# KlingelESP32V1.net
KiCad netlist of a schematic drawn in EAGLE
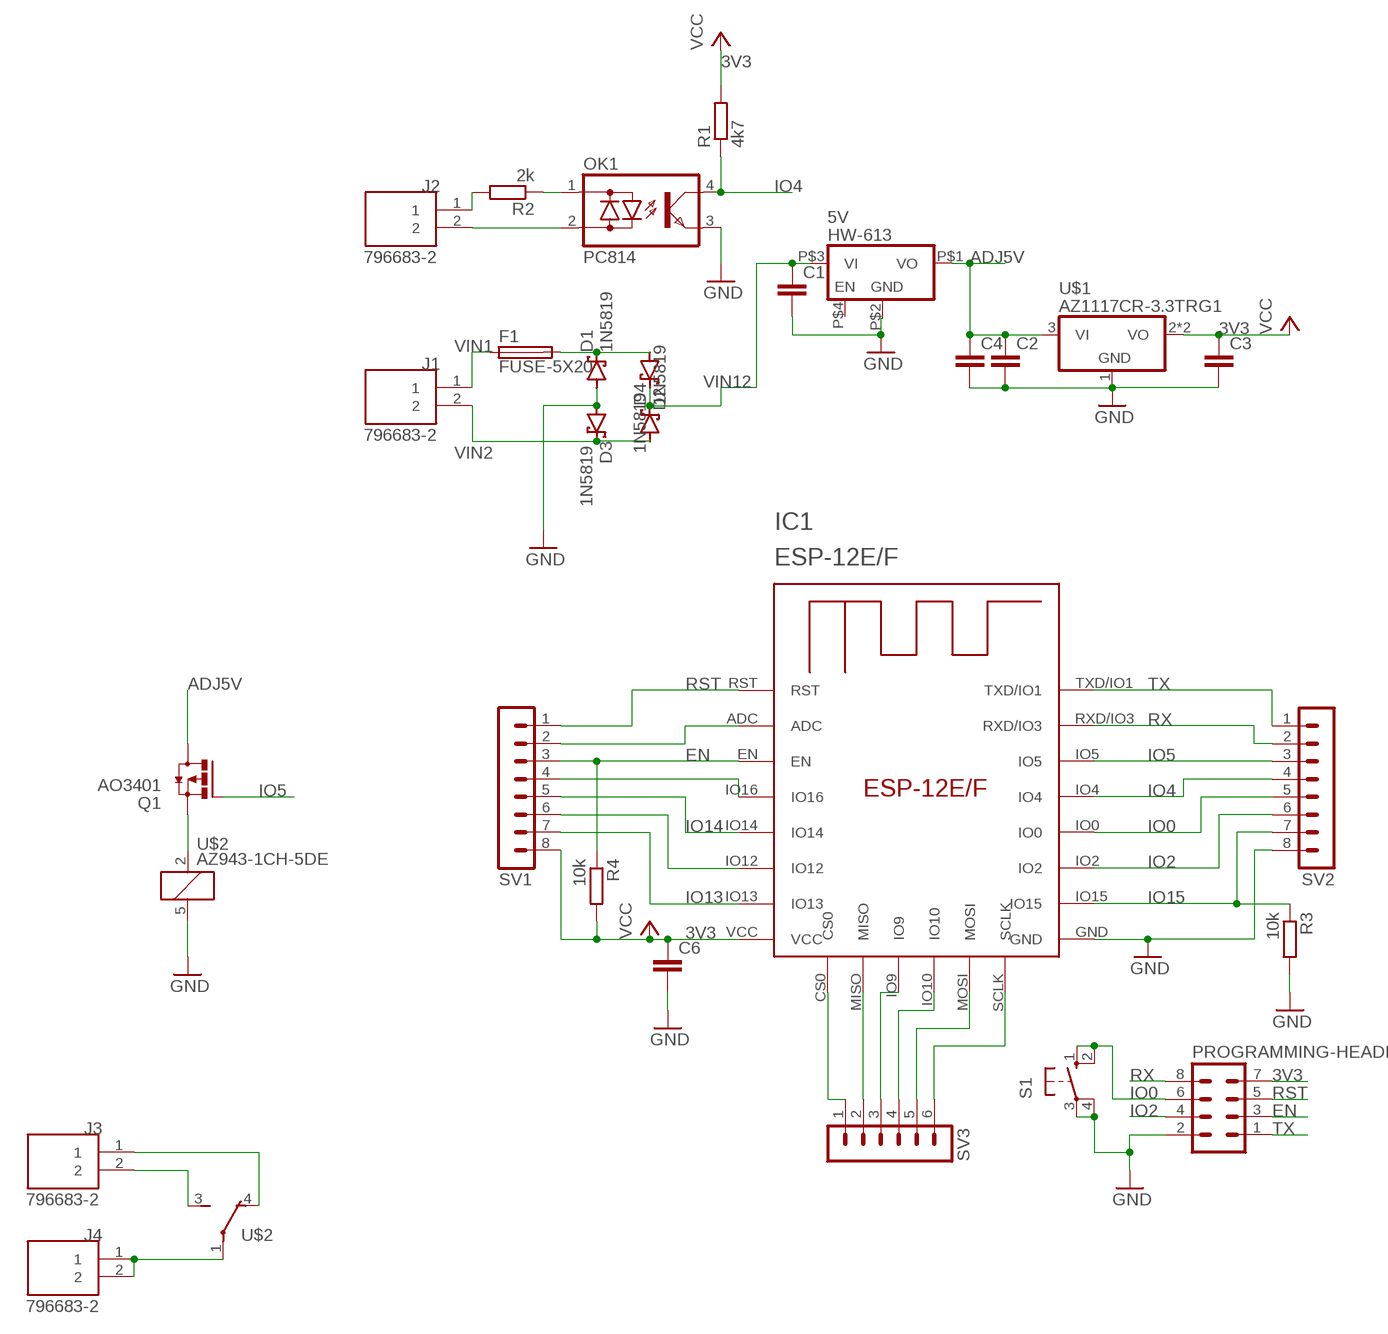
[diagram p0: schematic, sheet 1]

(export (version "E")
  (design (tool "Eeschema 10.0.6"))
  (components
    (comp (ref "5V")
      (value "HW-613")
      (footprint "eagle-import:HW-613")
      (libsource (lib "eagle-import") (part "HW-613"))
    )
    (comp (ref "C1")
      (value "C-EUC0805")
      (footprint "eagle-import:C0805")
      (libsource (lib "eagle-import") (part "C-EUC0805"))
    )
    (comp (ref "C2")
      (value "C-EUC0805")
      (footprint "eagle-import:C0805")
      (libsource (lib "eagle-import") (part "C-EUC0805"))
    )
    (comp (ref "C3")
      (value "C-EUC0805")
      (footprint "eagle-import:C0805")
      (libsource (lib "eagle-import") (part "C-EUC0805"))
    )
    (comp (ref "C4")
      (value "C-EUC0805")
      (footprint "eagle-import:C0805")
      (libsource (lib "eagle-import") (part "C-EUC0805"))
    )
    (comp (ref "C6")
      (value "C-EUC0805")
      (footprint "eagle-import:C0805")
      (libsource (lib "eagle-import") (part "C-EUC0805"))
    )
    (comp (ref "D1")
      (value "1N5819")
      (footprint "eagle-import:DO41-7.6")
      (libsource (lib "eagle-import") (part "1N5819-B"))
    )
    (comp (ref "D2")
      (value "1N5819")
      (footprint "eagle-import:DO41-7.6")
      (libsource (lib "eagle-import") (part "1N5819-B"))
    )
    (comp (ref "D3")
      (value "1N5819")
      (footprint "eagle-import:DO41-7.6")
      (libsource (lib "eagle-import") (part "1N5819-B"))
    )
    (comp (ref "D4")
      (value "1N5819")
      (footprint "eagle-import:DO41-7.6")
      (libsource (lib "eagle-import") (part "1N5819-B"))
    )
    (comp (ref "F1")
      (value "FUSE-5X20")
      (footprint "eagle-import:0751.0052")
      (libsource (lib "eagle-import") (part "FUSE-5X20"))
    )
    (comp (ref "IC1")
      (value "ESP-12E/F")
      (footprint "eagle-import:ESP-12E")
      (libsource (lib "eagle-import") (part "ESP-12E/F"))
    )
    (comp (ref "J1")
      (value "796683-2")
      (footprint "eagle-import:TE_796683-2")
      (fields (field (name "MF") "TE Connectivity"))
      (libsource (lib "eagle-import") (part "796683-2"))
    )
    (comp (ref "J2")
      (value "796683-2")
      (footprint "eagle-import:TE_796683-2")
      (fields (field (name "MF") "TE Connectivity"))
      (libsource (lib "eagle-import") (part "796683-2"))
    )
    (comp (ref "J3")
      (value "796683-2")
      (footprint "eagle-import:TE_796683-2")
      (fields (field (name "MF") "TE Connectivity"))
      (libsource (lib "eagle-import") (part "796683-2"))
    )
    (comp (ref "J4")
      (value "796683-2")
      (footprint "eagle-import:TE_796683-2")
      (fields (field (name "MF") "TE Connectivity"))
      (libsource (lib "eagle-import") (part "796683-2"))
    )
    (comp (ref "OK1")
      (value "PC814")
      (footprint "eagle-import:DIL04")
      (libsource (lib "eagle-import") (part "PC814"))
    )
    (comp (ref "PROGRAMMING-HEADER")
      (value "MA04-2")
      (footprint "eagle-import:MA04-2")
      (libsource (lib "eagle-import") (part "MA04-2"))
    )
    (comp (ref "Q1")
      (value "AO3401")
      (footprint "eagle-import:SUPER-SOT3")
      (libsource (lib "eagle-import") (part "FDN360P"))
    )
    (comp (ref "R1")
      (value "4k7")
      (footprint "eagle-import:R0805")
      (libsource (lib "eagle-import") (part "R-EU_R0805"))
    )
    (comp (ref "R2")
      (value "2k")
      (footprint "eagle-import:R0805")
      (libsource (lib "eagle-import") (part "R-EU_R0805"))
    )
    (comp (ref "R3")
      (value "10k")
      (footprint "eagle-import:R0805")
      (libsource (lib "eagle-import") (part "R-EU_R0805"))
    )
    (comp (ref "R4")
      (value "10k")
      (footprint "eagle-import:R0805")
      (libsource (lib "eagle-import") (part "R-EU_R0805"))
    )
    (comp (ref "S1")
      (value "10-XX")
      (footprint "eagle-import:B3F-10XX")
      (fields (field (name "MPN") "B3F-1000"))
      (libsource (lib "eagle-import") (part "10-XX"))
    )
    (comp (ref "SV1")
      (value "MA08-1")
      (footprint "eagle-import:MA08-1")
      (libsource (lib "eagle-import") (part "MA08-1"))
    )
    (comp (ref "SV2")
      (value "MA08-1")
      (footprint "eagle-import:MA08-1")
      (libsource (lib "eagle-import") (part "MA08-1"))
    )
    (comp (ref "SV3")
      (value "MA06-1")
      (footprint "eagle-import:MA06-1")
      (libsource (lib "eagle-import") (part "MA06-1"))
    )
    (comp (ref "U$1")
      (value "AZ1117CR-3.3TRG1")
      (footprint "eagle-import:SOT89")
      (libsource (lib "eagle-import") (part "AZ1117CR-3.3TRG1"))
    )
    (comp (ref "U$2")
      (value "AZ943-1CH-5DE")
      (footprint "eagle-import:AZ943-1CH-5DE")
      (libsource (lib "eagle-import") (part "AZ943-1CH-5DE"))
    )
  )
  (nets
    (net (code "1") (name "/ADJ5V") (class "Default")
      (node (ref "5V") (pin "P$1") (pinfunction "VO_P$1") (pintype "passive"))
      (node (ref "C2") (pin "1") (pinfunction "1_1") (pintype "passive"))
      (node (ref "C4") (pin "1") (pinfunction "1_1") (pintype "passive"))
      (node (ref "Q1") (pin "3") (pinfunction "D_3") (pintype "passive"))
      (node (ref "U$1") (pin "3") (pinfunction "VI_3") (pintype "input"))
    )
    (net (code "2") (name "/EN") (class "Default")
      (node (ref "IC1") (pin "EN") (pinfunction "EN_EN") (pintype "bidirectional"))
      (node (ref "PROGRAMMING-HEADER") (pin "3") (pinfunction "3_3") (pintype "passive"))
      (node (ref "R4") (pin "1") (pinfunction "1_1") (pintype "passive"))
      (node (ref "SV1") (pin "3") (pinfunction "3_3") (pintype "passive"))
    )
    (net (code "3") (name "/IO0") (class "Default")
      (node (ref "IC1") (pin "IO0") (pinfunction "IO0_IO0") (pintype "bidirectional"))
      (node (ref "PROGRAMMING-HEADER") (pin "6") (pinfunction "6_6") (pintype "passive"))
      (node (ref "S1") (pin "1") (pinfunction "S_1") (pintype "passive"))
      (node (ref "S1") (pin "2") (pinfunction "S1_2") (pintype "passive"))
      (node (ref "SV2") (pin "5") (pinfunction "5_5") (pintype "passive"))
    )
    (net (code "4") (name "/IO2") (class "Default")
      (node (ref "IC1") (pin "IO2") (pinfunction "IO2_IO2") (pintype "bidirectional"))
      (node (ref "PROGRAMMING-HEADER") (pin "4") (pinfunction "4_4") (pintype "passive"))
      (node (ref "SV2") (pin "6") (pinfunction "6_6") (pintype "passive"))
    )
    (net (code "5") (name "/IO4") (class "Default")
      (node (ref "IC1") (pin "IO4") (pinfunction "IO4_IO4") (pintype "bidirectional"))
      (node (ref "OK1") (pin "4") (pinfunction "C_4") (pintype "passive"))
      (node (ref "R1") (pin "1") (pinfunction "1_1") (pintype "passive"))
      (node (ref "SV2") (pin "4") (pinfunction "4_4") (pintype "passive"))
    )
    (net (code "6") (name "/IO5") (class "Default")
      (node (ref "IC1") (pin "IO5") (pinfunction "IO5_IO5") (pintype "bidirectional"))
      (node (ref "Q1") (pin "1") (pinfunction "G_1") (pintype "passive"))
      (node (ref "SV2") (pin "3") (pinfunction "3_3") (pintype "passive"))
    )
    (net (code "7") (name "/IO13") (class "Default")
      (node (ref "IC1") (pin "IO13") (pinfunction "IO13_IO13") (pintype "bidirectional"))
      (node (ref "SV1") (pin "7") (pinfunction "7_7") (pintype "passive"))
    )
    (net (code "8") (name "/IO14") (class "Default")
      (node (ref "IC1") (pin "IO14") (pinfunction "IO14_IO14") (pintype "bidirectional"))
      (node (ref "SV1") (pin "5") (pinfunction "5_5") (pintype "passive"))
    )
    (net (code "9") (name "/IO15") (class "Default")
      (node (ref "IC1") (pin "IO15") (pinfunction "IO15_IO15") (pintype "bidirectional"))
      (node (ref "R3") (pin "1") (pinfunction "1_1") (pintype "passive"))
      (node (ref "SV2") (pin "7") (pinfunction "7_7") (pintype "passive"))
    )
    (net (code "10") (name "/RST") (class "Default")
      (node (ref "IC1") (pin "RST") (pinfunction "RST_RST") (pintype "input"))
      (node (ref "PROGRAMMING-HEADER") (pin "5") (pinfunction "5_5") (pintype "passive"))
      (node (ref "SV1") (pin "1") (pinfunction "1_1") (pintype "passive"))
    )
    (net (code "11") (name "/RX") (class "Default")
      (node (ref "IC1") (pin "RXD/IO3") (pinfunction "RXD/IO3_RXD/IO3") (pintype "bidirectional"))
      (node (ref "PROGRAMMING-HEADER") (pin "8") (pinfunction "8_8") (pintype "passive"))
      (node (ref "SV2") (pin "2") (pinfunction "2_2") (pintype "passive"))
    )
    (net (code "12") (name "/TX") (class "Default")
      (node (ref "IC1") (pin "TXD/IO1") (pinfunction "TXD/IO1_TXD/IO1") (pintype "bidirectional"))
      (node (ref "PROGRAMMING-HEADER") (pin "1") (pinfunction "1_1") (pintype "passive"))
      (node (ref "SV2") (pin "1") (pinfunction "1_1") (pintype "passive"))
    )
    (net (code "13") (name "/VIN1") (class "Default")
      (node (ref "F1") (pin "P$1") (pinfunction "1_P$1") (pintype "passive"))
      (node (ref "F1") (pin "P$2") (pinfunction "1_P$2") (pintype "passive"))
      (node (ref "J1") (pin "1") (pinfunction "1_1") (pintype "passive"))
    )
    (net (code "14") (name "/VIN2") (class "Default")
      (node (ref "D3") (pin "C") (pinfunction "C_C") (pintype "passive"))
      (node (ref "D4") (pin "A") (pinfunction "A_A") (pintype "passive"))
      (node (ref "J1") (pin "2") (pinfunction "2_2") (pintype "passive"))
    )
    (net (code "15") (name "/VIN12") (class "Default")
      (node (ref "5V") (pin "P$3") (pinfunction "VI_P$3") (pintype "input"))
      (node (ref "C1") (pin "1") (pinfunction "1_1") (pintype "passive"))
      (node (ref "D2") (pin "C") (pinfunction "C_C") (pintype "passive"))
      (node (ref "D4") (pin "C") (pinfunction "C_C") (pintype "passive"))
    )
    (net (code "16") (name "GND") (class "Default")
      (node (ref "5V") (pin "P$2") (pinfunction "ADJ1_P$2") (pintype "power_in"))
      (node (ref "C1") (pin "2") (pinfunction "2_2") (pintype "passive"))
      (node (ref "C2") (pin "2") (pinfunction "2_2") (pintype "passive"))
      (node (ref "C3") (pin "2") (pinfunction "2_2") (pintype "passive"))
      (node (ref "C4") (pin "2") (pinfunction "2_2") (pintype "passive"))
      (node (ref "C6") (pin "2") (pinfunction "2_2") (pintype "passive"))
      (node (ref "D1") (pin "A") (pinfunction "A_A") (pintype "passive"))
      (node (ref "D3") (pin "A") (pinfunction "A_A") (pintype "passive"))
      (node (ref "IC1") (pin "GND") (pinfunction "GND_GND") (pintype "power_in"))
      (node (ref "OK1") (pin "3") (pinfunction "E_3") (pintype "passive"))
      (node (ref "PROGRAMMING-HEADER") (pin "2") (pinfunction "2_2") (pintype "passive"))
      (node (ref "R3") (pin "2") (pinfunction "2_2") (pintype "passive"))
      (node (ref "S1") (pin "3") (pinfunction "P_3") (pintype "passive"))
      (node (ref "S1") (pin "4") (pinfunction "P1_4") (pintype "passive"))
      (node (ref "SV2") (pin "8") (pinfunction "8_8") (pintype "passive"))
      (node (ref "U$1") (pin "1") (pinfunction "GND_1") (pintype "power_in"))
      (node (ref "U$2") (pin "5") (pinfunction "2_5") (pintype "passive"))
    )
    (net (code "17") (name "Net-(D1-PadC)") (class "Default")
      (node (ref "D1") (pin "C") (pinfunction "C_C") (pintype "passive"))
      (node (ref "D2") (pin "A") (pinfunction "A_A") (pintype "passive"))
      (node (ref "F1") (pin "P$3") (pinfunction "2_P$3") (pintype "passive"))
      (node (ref "F1") (pin "P$4") (pinfunction "2_P$4") (pintype "passive"))
    )
    (net (code "18") (name "Net-(IC1-PadADC)") (class "Default")
      (node (ref "IC1") (pin "ADC") (pinfunction "ADC_ADC") (pintype "bidirectional"))
      (node (ref "SV1") (pin "2") (pinfunction "2_2") (pintype "passive"))
    )
    (net (code "19") (name "Net-(IC1-PadCS0)") (class "Default")
      (node (ref "IC1") (pin "CS0") (pinfunction "CS0_CS0") (pintype "bidirectional"))
      (node (ref "SV3") (pin "1") (pinfunction "1_1") (pintype "passive"))
    )
    (net (code "20") (name "Net-(IC1-PadIO9)") (class "Default")
      (node (ref "IC1") (pin "IO9") (pinfunction "IO9_IO9") (pintype "bidirectional"))
      (node (ref "SV3") (pin "3") (pinfunction "3_3") (pintype "passive"))
    )
    (net (code "21") (name "Net-(IC1-PadIO10)") (class "Default")
      (node (ref "IC1") (pin "IO10") (pinfunction "IO10_IO10") (pintype "bidirectional"))
      (node (ref "SV3") (pin "4") (pinfunction "4_4") (pintype "passive"))
    )
    (net (code "22") (name "Net-(IC1-PadIO12)") (class "Default")
      (node (ref "IC1") (pin "IO12") (pinfunction "IO12_IO12") (pintype "bidirectional"))
      (node (ref "SV1") (pin "6") (pinfunction "6_6") (pintype "passive"))
    )
    (net (code "23") (name "Net-(IC1-PadIO16)") (class "Default")
      (node (ref "IC1") (pin "IO16") (pinfunction "IO16_IO16") (pintype "bidirectional"))
      (node (ref "SV1") (pin "4") (pinfunction "4_4") (pintype "passive"))
    )
    (net (code "24") (name "Net-(IC1-PadMISO)") (class "Default")
      (node (ref "IC1") (pin "MISO") (pinfunction "MISO_MISO") (pintype "bidirectional"))
      (node (ref "SV3") (pin "2") (pinfunction "2_2") (pintype "passive"))
    )
    (net (code "25") (name "Net-(IC1-PadMOSI)") (class "Default")
      (node (ref "IC1") (pin "MOSI") (pinfunction "MOSI_MOSI") (pintype "bidirectional"))
      (node (ref "SV3") (pin "5") (pinfunction "5_5") (pintype "passive"))
    )
    (net (code "26") (name "Net-(IC1-PadSCLK)") (class "Default")
      (node (ref "IC1") (pin "SCLK") (pinfunction "SCLK_SCLK") (pintype "bidirectional"))
      (node (ref "SV3") (pin "6") (pinfunction "6_6") (pintype "passive"))
    )
    (net (code "27") (name "Net-(J2-Pad1)") (class "Default")
      (node (ref "J2") (pin "1") (pinfunction "1_1") (pintype "passive"))
      (node (ref "R2") (pin "2") (pinfunction "2_2") (pintype "passive"))
    )
    (net (code "28") (name "Net-(OK1-AC1)") (class "Default")
      (node (ref "OK1") (pin "1") (pinfunction "AC1_1") (pintype "passive"))
      (node (ref "R2") (pin "1") (pinfunction "1_1") (pintype "passive"))
    )
    (net (code "29") (name "Net-(OK1-AC2)") (class "Default")
      (node (ref "J2") (pin "2") (pinfunction "2_2") (pintype "passive"))
      (node (ref "OK1") (pin "2") (pinfunction "AC2_2") (pintype "passive"))
    )
    (net (code "30") (name "Net-(Q1-S)") (class "Default")
      (node (ref "Q1") (pin "2") (pinfunction "S_2") (pintype "passive"))
      (node (ref "U$2") (pin "2") (pinfunction "1_2") (pintype "passive"))
    )
    (net (code "31") (name "Net-(U$2B-O)") (class "Default")
      (node (ref "J3") (pin "1") (pinfunction "1_1") (pintype "passive"))
      (node (ref "U$2") (pin "4") (pinfunction "O_4") (pintype "passive"))
    )
    (net (code "32") (name "Net-(U$2B-P)") (class "Default")
      (node (ref "J4") (pin "1") (pinfunction "1_1") (pintype "passive"))
      (node (ref "J4") (pin "2") (pinfunction "2_2") (pintype "passive"))
      (node (ref "U$2") (pin "1") (pinfunction "P_1") (pintype "passive"))
    )
    (net (code "33") (name "Net-(U$2B-S)") (class "Default")
      (node (ref "J3") (pin "2") (pinfunction "2_2") (pintype "passive"))
      (node (ref "U$2") (pin "3") (pinfunction "S_3") (pintype "passive"))
    )
    (net (code "34") (name "VCC") (class "Default")
      (node (ref "C3") (pin "1") (pinfunction "1_1") (pintype "passive"))
      (node (ref "C6") (pin "1") (pinfunction "1_1") (pintype "passive"))
      (node (ref "IC1") (pin "VCC") (pinfunction "VCC_VCC") (pintype "power_in"))
      (node (ref "PROGRAMMING-HEADER") (pin "7") (pinfunction "7_7") (pintype "passive"))
      (node (ref "R1") (pin "2") (pinfunction "2_2") (pintype "passive"))
      (node (ref "R4") (pin "2") (pinfunction "2_2") (pintype "passive"))
      (node (ref "SV1") (pin "8") (pinfunction "8_8") (pintype "passive"))
      (node (ref "U$1") (pin "2") (pinfunction "VO_2") (pintype "passive"))
      (node (ref "U$1") (pin "2@1") (pinfunction "VO_2@1") (pintype "passive"))
    )
    (net (code "35") (name "unconnected-(5V-ADJ-PadP$4)") (class "Default")
      (node (ref "5V") (pin "P$4") (pinfunction "ADJ_P$4") (pintype "input"))
    )
  )
)
